# bristlebot.net
KiCad netlist of a schematic drawn in EAGLE
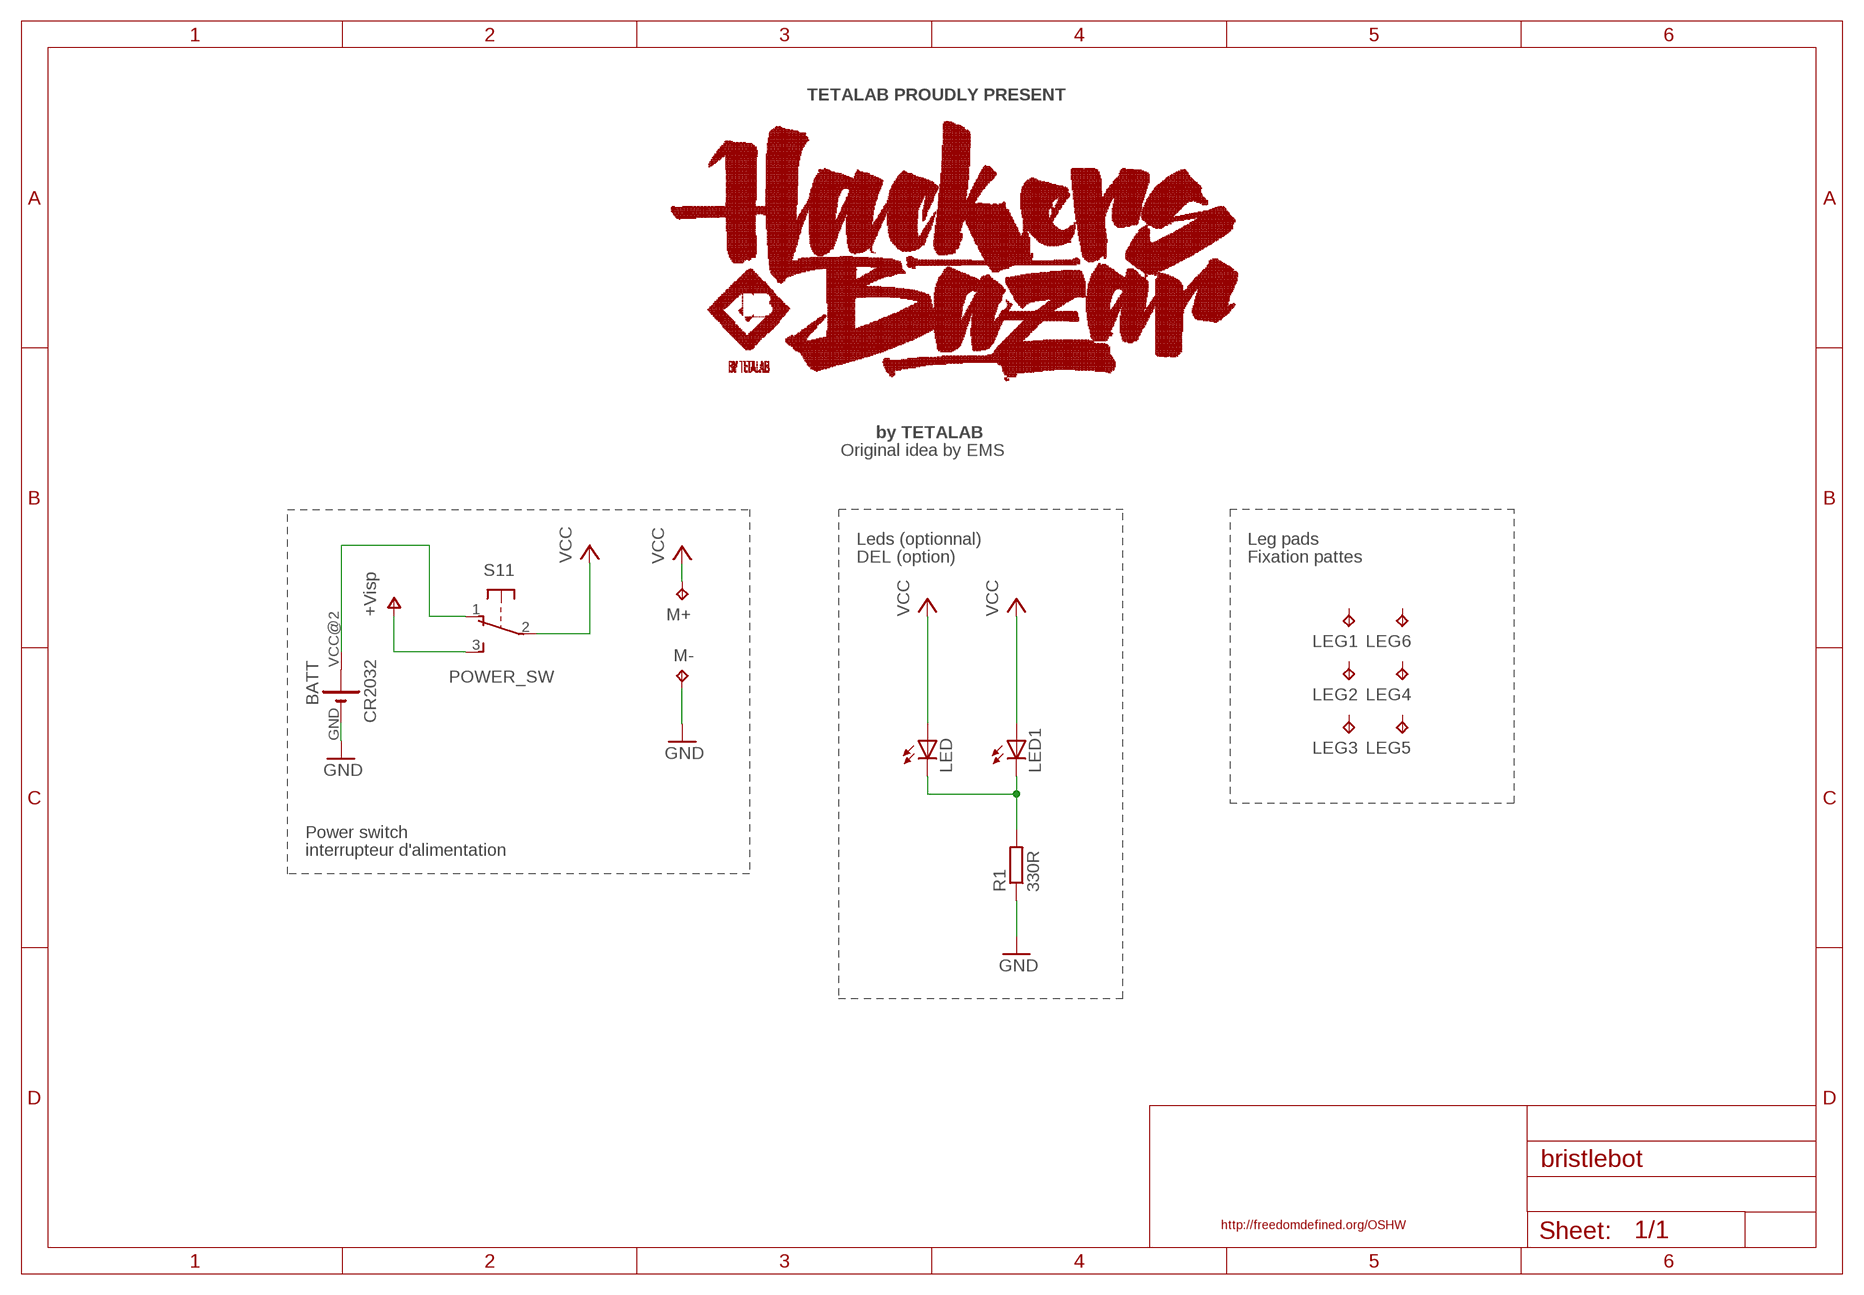
[diagram p0: schematic, sheet 1]

(export (version "E")
  (design (tool "Eeschema 10.0.6"))
  (components
    (comp (ref "BATT")
      (value "CR2032")
      (footprint "eagle-import:BATT_CONN_CR2032")
      (libsource (lib "eagle-import") (part "CR2032HCOMPACT"))
    )
    (comp (ref "LED")
      (value "LED3MM")
      (footprint "eagle-import:LED3MM")
      (libsource (lib "eagle-import") (part "LED3MM"))
    )
    (comp (ref "LED1")
      (value "LED3MM")
      (footprint "eagle-import:LED3MM")
      (libsource (lib "eagle-import") (part "LED3MM"))
    )
    (comp (ref "LEG1")
      (value "TPPAD0.8-2.5R")
      (footprint "eagle-import:P0.8-2.5")
      (libsource (lib "eagle-import") (part "TPPAD0.8-2.5R"))
    )
    (comp (ref "LEG2")
      (value "TPPAD0.8-2.5R")
      (footprint "eagle-import:P0.8-2.5")
      (libsource (lib "eagle-import") (part "TPPAD0.8-2.5R"))
    )
    (comp (ref "LEG3")
      (value "TPPAD0.8-2.5R")
      (footprint "eagle-import:P0.8-2.5")
      (libsource (lib "eagle-import") (part "TPPAD0.8-2.5R"))
    )
    (comp (ref "LEG4")
      (value "TPPAD0.8-2.5R")
      (footprint "eagle-import:P0.8-2.5")
      (libsource (lib "eagle-import") (part "TPPAD0.8-2.5R"))
    )
    (comp (ref "LEG5")
      (value "TPPAD0.8-2.5R")
      (footprint "eagle-import:P0.8-2.5")
      (libsource (lib "eagle-import") (part "TPPAD0.8-2.5R"))
    )
    (comp (ref "LEG6")
      (value "TPPAD0.8-2.5R")
      (footprint "eagle-import:P0.8-2.5")
      (libsource (lib "eagle-import") (part "TPPAD0.8-2.5R"))
    )
    (comp (ref "M+")
      (value "TPPAD0.8-2R")
      (footprint "eagle-import:P0.8-2")
      (libsource (lib "eagle-import") (part "TPPAD0.8-2R"))
    )
    (comp (ref "M-")
      (value "TPPAD0.8-2R")
      (footprint "eagle-import:P0.8-2")
      (libsource (lib "eagle-import") (part "TPPAD0.8-2R"))
    )
    (comp (ref "R1")
      (value "330R")
      (footprint "eagle-import:0207_7")
      (libsource (lib "eagle-import") (part "R-EU_0207/7"))
    )
    (comp (ref "S1")
      (value "POWER_SW")
      (footprint "eagle-import:OS102011MA1QN1")
      (libsource (lib "eagle-import") (part "SLIDING_SWITCH_SPDT-OS102011MA1QN1"))
    )
  )
  (nets
    (net (code "1") (name "+Visp") (class "Default")
      (node (ref "S1") (pin "3") (pinfunction "3_3") (pintype "passive"))
    )
    (net (code "2") (name "GND") (class "Default")
      (node (ref "BATT") (pin "GND") (pinfunction "-_GND") (pintype "passive"))
      (node (ref "M-") (pin "TP") (pinfunction "TP_TP") (pintype "input"))
      (node (ref "R1") (pin "1") (pinfunction "1_1") (pintype "passive"))
    )
    (net (code "3") (name "Net-(BATT-+-PadVCC@2)") (class "Default")
      (node (ref "BATT") (pin "VCC@2") (pinfunction "+_VCC@2") (pintype "passive"))
      (node (ref "S1") (pin "1") (pinfunction "1_1") (pintype "passive"))
    )
    (net (code "4") (name "Net-(LED-C)") (class "Default")
      (node (ref "LED") (pin "K") (pinfunction "C_K") (pintype "passive"))
      (node (ref "LED1") (pin "K") (pinfunction "C_K") (pintype "passive"))
      (node (ref "R1") (pin "2") (pinfunction "2_2") (pintype "passive"))
    )
    (net (code "5") (name "VCC") (class "Default")
      (node (ref "LED") (pin "A") (pinfunction "A_A") (pintype "passive"))
      (node (ref "LED1") (pin "A") (pinfunction "A_A") (pintype "passive"))
      (node (ref "M+") (pin "TP") (pinfunction "TP_TP") (pintype "input"))
      (node (ref "S1") (pin "2") (pinfunction "2_2") (pintype "passive"))
    )
    (net (code "6") (name "unconnected-(BATT-+-PadVCC@1)") (class "Default")
      (node (ref "BATT") (pin "VCC@1") (pinfunction "+_VCC@1") (pintype "passive"))
    )
    (net (code "7") (name "unconnected-(LEG1-PadTP)") (class "Default")
      (node (ref "LEG1") (pin "TP") (pinfunction "TP_TP") (pintype "input"))
    )
    (net (code "8") (name "unconnected-(LEG2-PadTP)") (class "Default")
      (node (ref "LEG2") (pin "TP") (pinfunction "TP_TP") (pintype "input"))
    )
    (net (code "9") (name "unconnected-(LEG3-PadTP)") (class "Default")
      (node (ref "LEG3") (pin "TP") (pinfunction "TP_TP") (pintype "input"))
    )
    (net (code "10") (name "unconnected-(LEG4-PadTP)") (class "Default")
      (node (ref "LEG4") (pin "TP") (pinfunction "TP_TP") (pintype "input"))
    )
    (net (code "11") (name "unconnected-(LEG5-PadTP)") (class "Default")
      (node (ref "LEG5") (pin "TP") (pinfunction "TP_TP") (pintype "input"))
    )
    (net (code "12") (name "unconnected-(LEG6-PadTP)") (class "Default")
      (node (ref "LEG6") (pin "TP") (pinfunction "TP_TP") (pintype "input"))
    )
  )
)
